# Power.net
KiCad netlist of a schematic drawn in Altium Designer
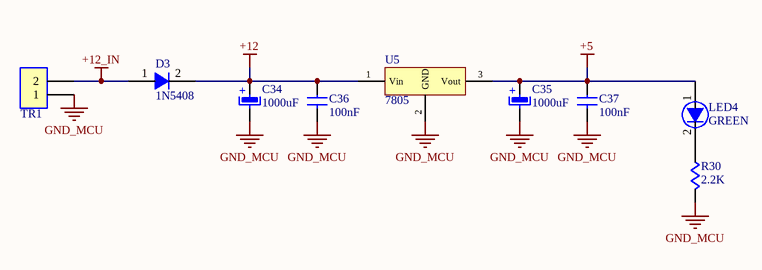
[diagram p0: Power.SchDoc]

(export (version "E")
  (design (tool "Eeschema 10.0.6"))
  (components
    (comp (ref "C34")
      (value "1000uF")
      (footprint "CAP-Elec-10x25-5")
      (description "CAPACITOR")
      (fields
        (field (name "VOLTAGE") "25V")
        (field (name "Comment") "CAP Elec 1000uF-25V-10x25-THD")
        (field (name "PUBLISHER") "Mahdi Bagherzadeh")
      )
      (libsource (lib "Mahdi-Bagherzadeh") (part "CAP-ELEC"))
    )
    (comp (ref "C35")
      (value "1000uF")
      (footprint "CAP-Elec-6.3x12")
      (description "CAPACITOR")
      (fields
        (field (name "VOLTAGE") "10V")
        (field (name "Comment") "CAP Elec 1000uF-10V-10x25-THD")
        (field (name "PUBLISHER") "Mahdi Bagherzadeh")
      )
      (libsource (lib "Mahdi-Bagherzadeh") (part "CAP-ELEC"))
    )
    (comp (ref "C36")
      (value "100nF")
      (footprint "C-0805")
      (description "CAPACITOR")
      (fields
        (field (name "VOLTAGE") "50V")
        (field (name "TOLERANCE") "X7R")
        (field (name "PUBLISHER") "Mahdi Bagherzadeh")
      )
      (libsource (lib "Mahdi-Bagherzadeh") (part "CAP-CER"))
    )
    (comp (ref "C37")
      (value "100nF")
      (footprint "C-0805")
      (description "CAPACITOR")
      (fields
        (field (name "VOLTAGE") "50V")
        (field (name "TOLERANCE") "X7R")
        (field (name "PUBLISHER") "Mahdi Bagherzadeh")
      )
      (libsource (lib "Mahdi-Bagherzadeh") (part "CAP-CER"))
    )
    (comp (ref "D3")
      (value "Diode 1N5408-SMD")
      (footprint "D-DO214")
      (description "DIODE")
      (fields (field (name "CODE") "1N5408") (field (name "PUBLISHER") "Mahdi Bagherzadeh"))
      (libsource (lib "Mahdi-Bagherzadeh") (part "DIODE"))
    )
    (comp (ref "LED4")
      (value "LED GREEN-1206-SMD")
      (footprint "LED-1206-Y")
      (description "LED")
      (fields (field (name "COLOR") "GREEN") (field (name "PUBLISHER") "Mahdi Bagherzadeh"))
      (libsource (lib "Mahdi-Bagherzadeh") (part "LED"))
    )
    (comp (ref "R30")
      (value "2.2K")
      (footprint "R-0805")
      (description "RESISTOR")
      (fields
        (field (name "TOLERANCE") "5%")
        (field (name "POWER") "1/8W")
        (field (name "PUBLISHER") "Mahdi Bagherzadeh")
      )
      (libsource (lib "Mahdi-Bagherzadeh") (part "RES"))
    )
    (comp (ref "TR1")
      (value "Terminal KF301-2Pin-5.08mm-Straight")
      (footprint "KF301-2pin")
      (description "TERMINAL")
      (fields (field (name "PUBLISHER") "Mahdi Bagherzadeh"))
      (libsource (lib "Mahdi-Bagherzadeh") (part "TEMINAL-2pin"))
    )
    (comp (ref "U5")
      (value "Reg 7805-5V-THD")
      (footprint "TO220-HEARSINK-1")
      (description "REGULATOR")
      (fields
        (field (name "VOLTAGE") "5V")
        (field (name "CODE") "7805")
        (field (name "PUBLISHER") "Mahdi Bagherzadeh")
      )
      (libsource (lib "Mahdi-Bagherzadeh") (part "78Mxx"))
    )
  )
  (nets
    (net (code "1") (name "+5") (class "Default")
      (node (ref "C35") (pin "1") (pinfunction "1_1") (pintype "passive"))
      (node (ref "C37") (pin "1") (pinfunction "1_1") (pintype "passive"))
      (node (ref "LED4") (pin "1") (pinfunction "A_1") (pintype "passive"))
      (node (ref "U5") (pin "3") (pinfunction "Vout_3") (pintype "power_in"))
    )
    (net (code "2") (name "+12") (class "Default")
      (node (ref "C34") (pin "1") (pinfunction "1_1") (pintype "passive"))
      (node (ref "C36") (pin "1") (pinfunction "1_1") (pintype "passive"))
      (node (ref "D3") (pin "2") (pinfunction "C_2") (pintype "passive"))
      (node (ref "U5") (pin "1") (pinfunction "Vin_1") (pintype "power_in"))
    )
    (net (code "3") (name "+12_IN") (class "Default")
      (node (ref "D3") (pin "1") (pinfunction "A_1") (pintype "passive"))
      (node (ref "TR1") (pin "2") (pinfunction "2_2") (pintype "passive"))
    )
    (net (code "4") (name "GND_MCU") (class "Default")
      (node (ref "C34") (pin "2") (pinfunction "2_2") (pintype "passive"))
      (node (ref "C35") (pin "2") (pinfunction "2_2") (pintype "passive"))
      (node (ref "C36") (pin "2") (pinfunction "2_2") (pintype "passive"))
      (node (ref "C37") (pin "2") (pinfunction "2_2") (pintype "passive"))
      (node (ref "R30") (pin "2") (pinfunction "2_2") (pintype "passive"))
      (node (ref "TR1") (pin "1") (pinfunction "1_1") (pintype "passive"))
      (node (ref "U5") (pin "2") (pinfunction "GND_2") (pintype "power_in"))
    )
    (net (code "5") (name "Net-(LED4-C)") (class "Default")
      (node (ref "LED4") (pin "2") (pinfunction "C_2") (pintype "passive"))
      (node (ref "R30") (pin "1") (pinfunction "1_1") (pintype "passive"))
    )
  )
)
